# STM_BLUEPILL.net
KiCad netlist of a schematic drawn in Altium Designer
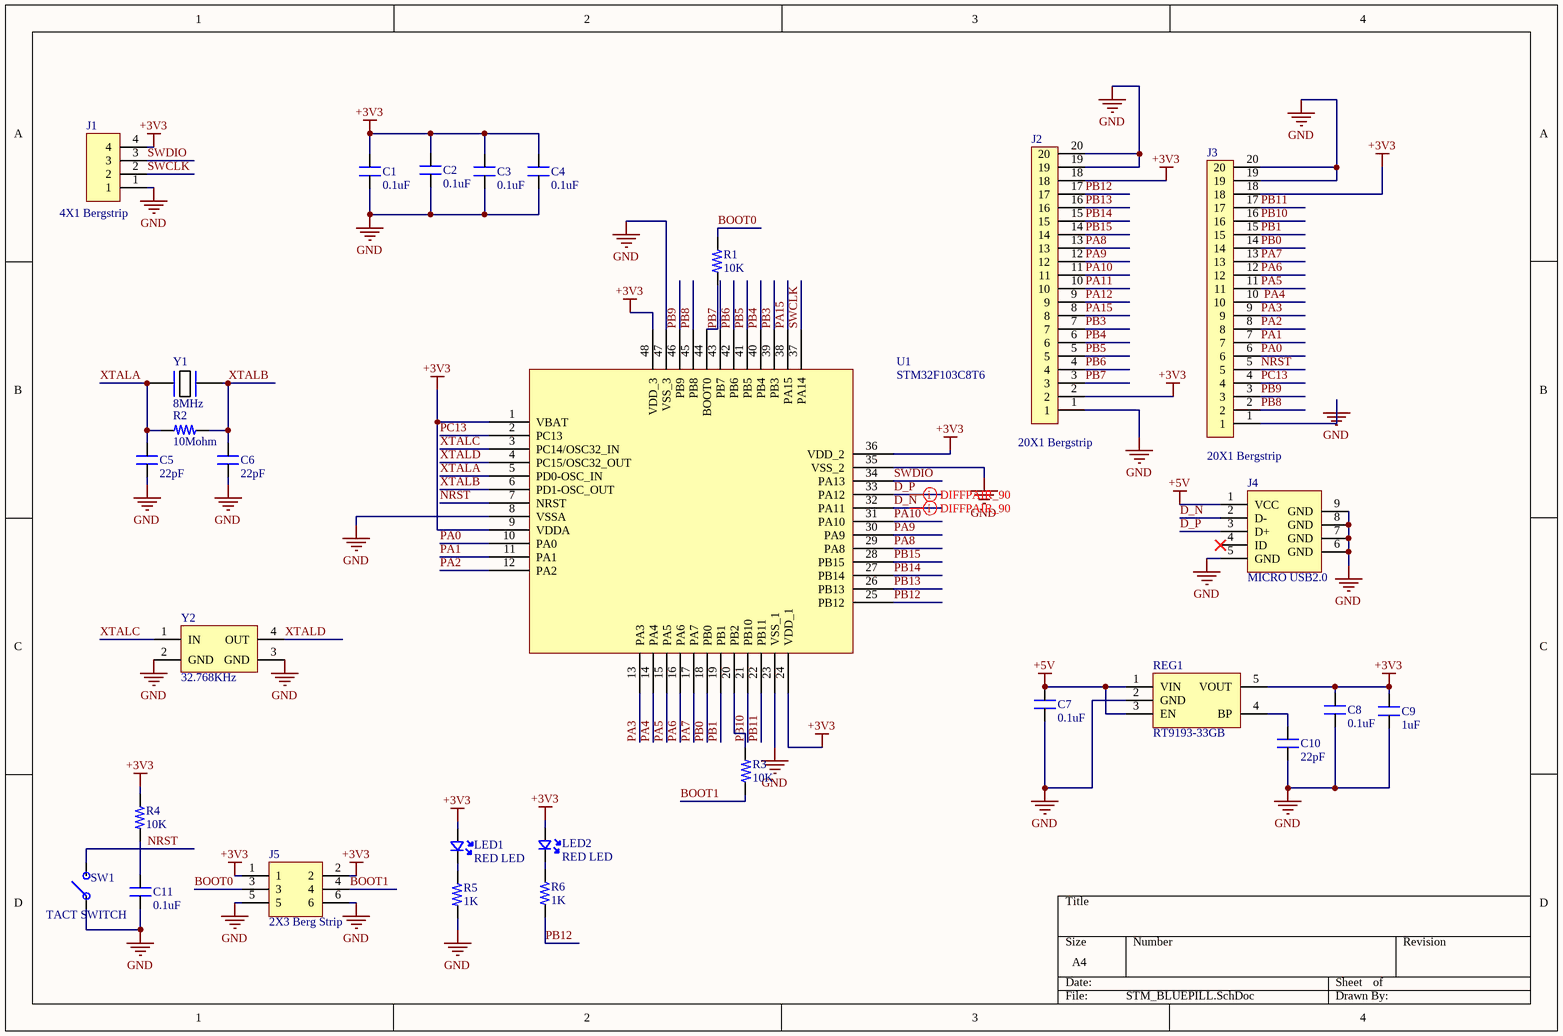
[diagram p0: STM_BLUEPILL.SchDoc]

(export (version "E")
  (design (tool "Eeschema 10.0.6"))
  (components
    (comp (ref "C1")
      (value "0.1uF")
      (footprint "CAP_0805")
      (description "0.1µF ±5% 50V Ceramic Capacitor X7R 0805 (2012 Metric)")
      (fields
        (field (name "MANUFACTURER") "KEMET")
        (field (name "MANUFACTURING PART NUMBER") "C0805C104J5RACTU")
      )
      (libsource (lib "STM_SCH_LIB") (part "CAP_0.1uF-50V-5%-0805"))
    )
    (comp (ref "C2")
      (value "0.1uF")
      (footprint "CAP_0805")
      (description "0.1µF ±5% 50V Ceramic Capacitor X7R 0805 (2012 Metric)")
      (fields
        (field (name "MANUFACTURER") "KEMET")
        (field (name "MANUFACTURING PART NUMBER") "C0805C104J5RACTU")
      )
      (libsource (lib "STM_SCH_LIB") (part "CAP_0.1uF-50V-5%-0805"))
    )
    (comp (ref "C3")
      (value "0.1uF")
      (footprint "CAP_0805")
      (description "0.1µF ±5% 50V Ceramic Capacitor X7R 0805 (2012 Metric)")
      (fields
        (field (name "MANUFACTURER") "KEMET")
        (field (name "MANUFACTURING PART NUMBER") "C0805C104J5RACTU")
      )
      (libsource (lib "STM_SCH_LIB") (part "CAP_0.1uF-50V-5%-0805"))
    )
    (comp (ref "C4")
      (value "0.1uF")
      (footprint "CAP_0805")
      (description "0.1µF ±5% 50V Ceramic Capacitor X7R 0805 (2012 Metric)")
      (fields
        (field (name "MANUFACTURER") "KEMET")
        (field (name "MANUFACTURING PART NUMBER") "C0805C104J5RACTU")
      )
      (libsource (lib "STM_SCH_LIB") (part "CAP_0.1uF-50V-5%-0805"))
    )
    (comp (ref "C5")
      (value "22pF")
      (footprint "CAP_0805")
      (description "22pF ±5% 50V Ceramic Capacitor C0G, NP0 0805 (2012 Metric)")
      (fields
        (field (name "MANUFACTURER") "KEMET")
        (field (name "MANUFACTURER PART NUMBER") "C0805C220J5GACTU")
      )
      (libsource (lib "STM_SCH_LIB") (part "CAP_22pF-50V-5%-0805"))
    )
    (comp (ref "C6")
      (value "22pF")
      (footprint "CAP_0805")
      (description "22pF ±5% 50V Ceramic Capacitor C0G, NP0 0805 (2012 Metric)")
      (fields
        (field (name "MANUFACTURER") "KEMET")
        (field (name "MANUFACTURER PART NUMBER") "C0805C220J5GACTU")
      )
      (libsource (lib "STM_SCH_LIB") (part "CAP_22pF-50V-5%-0805"))
    )
    (comp (ref "C7")
      (value "0.1uF")
      (footprint "CAP_0805")
      (description "0.1µF ±5% 50V Ceramic Capacitor X7R 0805 (2012 Metric)")
      (fields
        (field (name "MANUFACTURER") "KEMET")
        (field (name "MANUFACTURING PART NUMBER") "C0805C104J5RACTU")
      )
      (libsource (lib "STM_SCH_LIB") (part "CAP_0.1uF-50V-5%-0805"))
    )
    (comp (ref "C8")
      (value "0.1uF")
      (footprint "CAP_0805")
      (description "0.1µF ±5% 50V Ceramic Capacitor X7R 0805 (2012 Metric)")
      (fields
        (field (name "MANUFACTURER") "KEMET")
        (field (name "MANUFACTURING PART NUMBER") "C0805C104J5RACTU")
      )
      (libsource (lib "STM_SCH_LIB") (part "CAP_0.1uF-50V-5%-0805"))
    )
    (comp (ref "C9")
      (value "1uF")
      (footprint "CAP_0805")
      (description "1µF ±5% 50V Ceramic Capacitor X7R 0805 (2012 Metric)")
      (fields
        (field (name "MANUFACTURER") "Yageo")
        (field (name "MANUFACTURING PART NUMBER") "CC0805JKX7R9BB105")
      )
      (libsource (lib "STM_SCH_LIB") (part "CAP_1uF-50V-5%-0805"))
    )
    (comp (ref "C10")
      (value "22pF")
      (footprint "CAP_0805")
      (description "22pF ±5% 50V Ceramic Capacitor C0G, NP0 0805 (2012 Metric)")
      (fields
        (field (name "MANUFACTURER") "KEMET")
        (field (name "MANUFACTURER PART NUMBER") "C0805C220J5GACTU")
      )
      (libsource (lib "STM_SCH_LIB") (part "CAP_22pF-50V-5%-0805"))
    )
    (comp (ref "C11")
      (value "0.1uF")
      (footprint "CAP_0805")
      (description "0.1µF ±5% 50V Ceramic Capacitor X7R 0805 (2012 Metric)")
      (fields
        (field (name "MANUFACTURER") "KEMET")
        (field (name "MANUFACTURING PART NUMBER") "C0805C104J5RACTU")
      )
      (libsource (lib "STM_SCH_LIB") (part "CAP_0.1uF-50V-5%-0805"))
    )
    (comp (ref "J1")
      (value "4X1 Bergstrip")
      (footprint "CON4_100_40D72_TH_ST_MALE")
      (description "4 pin, 1 row, 2.54mm pitch bergstrip")
      (fields (field (name "MANUFACTURER") "NA"))
      (libsource (lib "STM_SCH_LIB") (part "CON-BS-PLG_4X1-100-TH-ST"))
    )
    (comp (ref "J2")
      (value "20X1 Bergstrip")
      (footprint "CON20_100_40D72_TH_ST")
      (description "20 pin, 1 row, 2.54mm pitch bergstrip")
      (fields (field (name "MANUFACTURER") "NA"))
      (libsource (lib "STM_SCH_LIB") (part "CON-BS-PLG_20X1-100-TH-ST"))
    )
    (comp (ref "J3")
      (value "20X1 Bergstrip")
      (footprint "CON20_100_40D72_TH_ST")
      (description "20 pin, 1 row, 2.54mm pitch bergstrip")
      (fields (field (name "MANUFACTURER") "NA"))
      (libsource (lib "STM_SCH_LIB") (part "CON-BS-PLG_20X1-100-TH-ST"))
    )
    (comp (ref "J4")
      (value "MICRO USB2.0")
      (footprint "CON_10118192-0001LF_SMD")
      (description "USB - micro B USB 2.0 Receptacle Connector 5 Position Surface Mount, Right Angle")
      (fields
        (field (name "MANUFACTURER") "Amphenol ICC (FCI)")
        (field (name "MANUFACTURING PART NUMBER") "10118192-0002LF")
      )
      (libsource (lib "STM_SCH_LIB") (part "CON-USB_10118192-0002LF-SMD"))
    )
    (comp (ref "J5")
      (value "2X3 Berg Strip")
      (footprint "CON6_100_59D78_TH_ST_Duplicate")
      (description "6 pin, 2 row, 2.54mm pitch bergstrip")
      (fields (field (name "MANUFACTURER") "NA"))
      (libsource (lib "STM_SCH_LIB") (part "CON-BS-PLG_2X3-100-TH-ST"))
    )
    (comp (ref "LED1")
      (value "RED LED")
      (footprint "LED_0805")
      (description "Red 621nm LED Indication - Discrete 2V 0805 (2012 Metric)")
      (fields
        (field (name "MANUFACTURER") "Lite-On Inc.")
        (field (name "MANUFACTURER PART NUMBER") "LTST-C170EKT")
      )
      (libsource (lib "STM_SCH_LIB") (part "LED-RED_10mA-0805"))
    )
    (comp (ref "LED2")
      (value "RED LED")
      (footprint "LED_0805")
      (description "Red 621nm LED Indication - Discrete 2V 0805 (2012 Metric)")
      (fields
        (field (name "MANUFACTURER") "Lite-On Inc.")
        (field (name "MANUFACTURER PART NUMBER") "LTST-C170EKT")
      )
      (libsource (lib "STM_SCH_LIB") (part "LED-RED_10mA-0805"))
    )
    (comp (ref "R1")
      (value "10K")
      (footprint "RES_0805")
      (description "10 kOhms ±1% 0.125W, 1/8W Chip Resistor 0805 (2012 Metric) Moisture Resistant Thick Film")
      (fields
        (field (name "MANUFACTURER") "Yageo")
        (field (name "MANUFACTURING PART NUMBER") "RC0805FR-0710KL")
      )
      (libsource (lib "STM_SCH_LIB") (part "RES_10K-0.125W-1%-0805"))
    )
    (comp (ref "R2")
      (value "10Mohm")
      (footprint "RES_0805")
      (fields
        (field (name "MANUFACTURER") "Rohm Semiconductor")
        (field (name "MANUFACTURING PART NUMBER") "KTR10EZPF1005")
      )
      (libsource (lib "STM_SCH_LIB") (part "RES_10MOHM-0.125W-1%-0805"))
    )
    (comp (ref "R3")
      (value "10K")
      (footprint "RES_0805")
      (description "10 kOhms ±1% 0.125W, 1/8W Chip Resistor 0805 (2012 Metric) Moisture Resistant Thick Film")
      (fields
        (field (name "MANUFACTURER") "Yageo")
        (field (name "MANUFACTURING PART NUMBER") "RC0805FR-0710KL")
      )
      (libsource (lib "STM_SCH_LIB") (part "RES_10K-0.125W-1%-0805"))
    )
    (comp (ref "R4")
      (value "10K")
      (footprint "RES_0805")
      (description "10 kOhms ±1% 0.125W, 1/8W Chip Resistor 0805 (2012 Metric) Moisture Resistant Thick Film")
      (fields
        (field (name "MANUFACTURER") "Yageo")
        (field (name "MANUFACTURING PART NUMBER") "RC0805FR-0710KL")
      )
      (libsource (lib "STM_SCH_LIB") (part "RES_10K-0.125W-1%-0805"))
    )
    (comp (ref "R5")
      (value "1K")
      (footprint "RES_0805")
      (description "1 kOhms ±1% 0.125W, 1/8W Chip Resistor 0805 (2012 Metric) Moisture Resistant Thick Film")
      (fields (field (name "MANUFACTURER") "垈㎵á") (field (name "MANUFACTURER PART NUMBER") "RC0805FR-071KL"))
      (libsource (lib "STM_SCH_LIB") (part "RES_1K-0.125W-1%-0805"))
    )
    (comp (ref "R6")
      (value "1K")
      (footprint "RES_0805")
      (description "1 kOhms ±1% 0.125W, 1/8W Chip Resistor 0805 (2012 Metric) Moisture Resistant Thick Film")
      (fields (field (name "MANUFACTURER") "垈㎵á") (field (name "MANUFACTURER PART NUMBER") "RC0805FR-071KL"))
      (libsource (lib "STM_SCH_LIB") (part "RES_1K-0.125W-1%-0805"))
    )
    (comp (ref "REG1")
      (value "RT9193-33GB")
      (footprint "SOT23-5")
      (description "Linear Voltage Regulator IC 1 Output 300mA SOT-23-5")
      (fields (field (name "MANUFACTURER") "Richtek USA Inc."))
      (libsource (lib "STM_SCH_LIB") (part "REG_3.3V-5.5V-0.3A-SOT-23-5"))
    )
    (comp (ref "SW1")
      (value "TACT SWITCH")
      (footprint "SW_342_SMD")
      (description "Tactile Switch SPST-NO Top Actuated Surface Mount")
      (fields (field (name "MANUFACTURER") "C&K") (field (name "MANUFACTURING PART NUMBER") "KSR223GLFG"))
      (libsource (lib "STM_SCH_LIB") (part "SW_KSR223GLFG-SMD"))
    )
    (comp (ref "U1")
      (value "STM32F103C8T6")
      (footprint "LQFP-48_19.6_393_58X11_SMD")
      (description "ARM® Cortex®-M3 STM32F1 Microcontroller IC 32-Bit 72MHz 64KB (64K x 8) FLASH")
      (fields (field (name "MANUFACTURER") "STMicroelectronics"))
      (libsource (lib "STM_SCH_LIB") (part "IC-STM32F103C8T6 _1"))
    )
    (comp (ref "Y1")
      (value "8MHz")
      (footprint "XTAL_314_240X47_SMD")
      (description "Crystals 8MHz 22pF -20C 70C")
      (fields
        (field (name "MANUFACTURER") "IQD Frequency Products")
        (field (name "MANUFACTURING PART NUMBER") "LFXTAL030234Reel")
      )
      (libsource (lib "STM_SCH_LIB") (part "XTAL_8MHZ-LFXTAL030234"))
    )
    (comp (ref "Y2")
      (value "32.768KHz")
      (footprint "XTAL_MC-405 32.7680K-G3")
      (description "Crystals SMD AT XTL MHZ +/-50PPM 12.5 PF 250 T/R")
      (fields
        (field (name "MANUFACTURER") "Epson")
        (field (name "MANUFACTURING PART NUMBER") "MC-405 32.7680K-G3: ROHS")
      )
      (libsource (lib "STM_SCH_LIB") (part "XTAL_32.768KHz-MC-405 32.7680K-G3"))
    )
  )
  (nets
    (net (code "1") (name "+3V3") (class "Default")
      (node (ref "C1") (pin "2") (pinfunction "2_2") (pintype "passive"))
      (node (ref "C2") (pin "2") (pinfunction "2_2") (pintype "passive"))
      (node (ref "C3") (pin "2") (pinfunction "2_2") (pintype "passive"))
      (node (ref "C4") (pin "2") (pinfunction "2_2") (pintype "passive"))
      (node (ref "C8") (pin "2") (pinfunction "2_2") (pintype "passive"))
      (node (ref "C9") (pin "2") (pinfunction "2_2") (pintype "passive"))
      (node (ref "J1") (pin "4") (pinfunction "4_4") (pintype "passive"))
      (node (ref "J2") (pin "18") (pinfunction "18_18") (pintype "passive"))
      (node (ref "J2") (pin "2") (pinfunction "2_2") (pintype "passive"))
      (node (ref "J3") (pin "18") (pinfunction "18_18") (pintype "passive"))
      (node (ref "J5") (pin "1") (pinfunction "1_1") (pintype "passive"))
      (node (ref "J5") (pin "2") (pinfunction "2_2") (pintype "passive"))
      (node (ref "LED1") (pin "A") (pinfunction "A_A") (pintype "passive"))
      (node (ref "LED2") (pin "A") (pinfunction "A_A") (pintype "passive"))
      (node (ref "R4") (pin "2") (pinfunction "2_2") (pintype "passive"))
      (node (ref "REG1") (pin "5") (pinfunction "VOUT_5") (pintype "passive"))
      (node (ref "U1") (pin "1") (pinfunction "VBAT_1") (pintype "passive"))
      (node (ref "U1") (pin "24") (pinfunction "VDD_1_24") (pintype "passive"))
      (node (ref "U1") (pin "36") (pinfunction "VDD_2_36") (pintype "passive"))
      (node (ref "U1") (pin "48") (pinfunction "VDD_3_48") (pintype "passive"))
      (node (ref "U1") (pin "9") (pinfunction "VDDA_9") (pintype "passive"))
    )
    (net (code "2") (name "+5V") (class "Default")
      (node (ref "C7") (pin "2") (pinfunction "2_2") (pintype "passive"))
      (node (ref "J4") (pin "1") (pinfunction "VCC_1") (pintype "passive"))
      (node (ref "REG1") (pin "1") (pinfunction "VIN_1") (pintype "passive"))
      (node (ref "REG1") (pin "3") (pinfunction "EN_3") (pintype "passive"))
    )
    (net (code "3") (name "/BOOT0") (class "Default")
      (node (ref "J5") (pin "3") (pinfunction "3_3") (pintype "passive"))
      (node (ref "R1") (pin "2") (pinfunction "2_2") (pintype "passive"))
    )
    (net (code "4") (name "/BOOT1") (class "Default")
      (node (ref "J5") (pin "4") (pinfunction "4_4") (pintype "passive"))
      (node (ref "R3") (pin "2") (pinfunction "2_2") (pintype "passive"))
    )
    (net (code "5") (name "/D_N") (class "Default")
      (node (ref "U1") (pin "32") (pinfunction "PA11_32") (pintype "passive"))
    )
    (net (code "6") (name "/D_P") (class "Default")
      (node (ref "J4") (pin "3") (pinfunction "D+_3") (pintype "passive"))
      (node (ref "U1") (pin "33") (pinfunction "PA12_33") (pintype "passive"))
    )
    (net (code "7") (name "/D_~{N}") (class "Default")
      (node (ref "J4") (pin "2") (pinfunction "D-_2") (pintype "passive"))
    )
    (net (code "8") (name "/NRST") (class "Default")
      (node (ref "J3") (pin "5") (pinfunction "5_5") (pintype "passive"))
      (node (ref "SW1") (pin "2") (pinfunction "2_2") (pintype "passive"))
      (node (ref "U1") (pin "7") (pinfunction "NRST_7") (pintype "passive"))
    )
    (net (code "9") (name "/PA0") (class "Default")
      (node (ref "J3") (pin "6") (pinfunction "6_6") (pintype "passive"))
      (node (ref "U1") (pin "10") (pinfunction "PA0_10") (pintype "passive"))
    )
    (net (code "10") (name "/PA1") (class "Default")
      (node (ref "J3") (pin "7") (pinfunction "7_7") (pintype "passive"))
      (node (ref "U1") (pin "11") (pinfunction "PA1_11") (pintype "passive"))
    )
    (net (code "11") (name "/PA2") (class "Default")
      (node (ref "J3") (pin "8") (pinfunction "8_8") (pintype "passive"))
      (node (ref "U1") (pin "12") (pinfunction "PA2_12") (pintype "passive"))
    )
    (net (code "12") (name "/PA3") (class "Default")
      (node (ref "J3") (pin "9") (pinfunction "9_9") (pintype "passive"))
      (node (ref "U1") (pin "13") (pinfunction "PA3_13") (pintype "passive"))
    )
    (net (code "13") (name "/PA4") (class "Default")
      (node (ref "J3") (pin "10") (pinfunction "10_10") (pintype "passive"))
      (node (ref "U1") (pin "14") (pinfunction "PA4_14") (pintype "passive"))
    )
    (net (code "14") (name "/PA5") (class "Default")
      (node (ref "J3") (pin "11") (pinfunction "11_11") (pintype "passive"))
      (node (ref "U1") (pin "15") (pinfunction "PA5_15") (pintype "passive"))
    )
    (net (code "15") (name "/PA6") (class "Default")
      (node (ref "J3") (pin "12") (pinfunction "12_12") (pintype "passive"))
      (node (ref "U1") (pin "16") (pinfunction "PA6_16") (pintype "passive"))
    )
    (net (code "16") (name "/PA7") (class "Default")
      (node (ref "J3") (pin "13") (pinfunction "13_13") (pintype "passive"))
      (node (ref "U1") (pin "17") (pinfunction "PA7_17") (pintype "passive"))
    )
    (net (code "17") (name "/PA8") (class "Default")
      (node (ref "J2") (pin "13") (pinfunction "13_13") (pintype "passive"))
      (node (ref "U1") (pin "29") (pinfunction "PA8_29") (pintype "passive"))
    )
    (net (code "18") (name "/PA9") (class "Default")
      (node (ref "J2") (pin "12") (pinfunction "12_12") (pintype "passive"))
      (node (ref "U1") (pin "30") (pinfunction "PA9_30") (pintype "passive"))
    )
    (net (code "19") (name "/PA10") (class "Default")
      (node (ref "J2") (pin "11") (pinfunction "11_11") (pintype "passive"))
      (node (ref "U1") (pin "31") (pinfunction "PA10_31") (pintype "passive"))
    )
    (net (code "20") (name "/PA11") (class "Default")
      (node (ref "J2") (pin "10") (pinfunction "10_10") (pintype "passive"))
    )
    (net (code "21") (name "/PA12") (class "Default")
      (node (ref "J2") (pin "9") (pinfunction "9_9") (pintype "passive"))
    )
    (net (code "22") (name "/PA15") (class "Default")
      (node (ref "J2") (pin "8") (pinfunction "8_8") (pintype "passive"))
      (node (ref "U1") (pin "38") (pinfunction "PA15_38") (pintype "passive"))
    )
    (net (code "23") (name "/PB0") (class "Default")
      (node (ref "J3") (pin "14") (pinfunction "14_14") (pintype "passive"))
      (node (ref "U1") (pin "18") (pinfunction "PB0_18") (pintype "passive"))
    )
    (net (code "24") (name "/PB1") (class "Default")
      (node (ref "J3") (pin "15") (pinfunction "15_15") (pintype "passive"))
      (node (ref "U1") (pin "19") (pinfunction "PB1_19") (pintype "passive"))
    )
    (net (code "25") (name "/PB3") (class "Default")
      (node (ref "J2") (pin "7") (pinfunction "7_7") (pintype "passive"))
      (node (ref "U1") (pin "39") (pinfunction "PB3_39") (pintype "passive"))
    )
    (net (code "26") (name "/PB4") (class "Default")
      (node (ref "J2") (pin "6") (pinfunction "6_6") (pintype "passive"))
      (node (ref "U1") (pin "40") (pinfunction "PB4_40") (pintype "passive"))
    )
    (net (code "27") (name "/PB5") (class "Default")
      (node (ref "J2") (pin "5") (pinfunction "5_5") (pintype "passive"))
      (node (ref "U1") (pin "41") (pinfunction "PB5_41") (pintype "passive"))
    )
    (net (code "28") (name "/PB6") (class "Default")
      (node (ref "J2") (pin "4") (pinfunction "4_4") (pintype "passive"))
      (node (ref "U1") (pin "42") (pinfunction "PB6_42") (pintype "passive"))
    )
    (net (code "29") (name "/PB7") (class "Default")
      (node (ref "J2") (pin "3") (pinfunction "3_3") (pintype "passive"))
      (node (ref "U1") (pin "43") (pinfunction "PB7_43") (pintype "passive"))
    )
    (net (code "30") (name "/PB8") (class "Default")
      (node (ref "J3") (pin "2") (pinfunction "2_2") (pintype "passive"))
      (node (ref "U1") (pin "45") (pinfunction "PB8_45") (pintype "passive"))
    )
    (net (code "31") (name "/PB9") (class "Default")
      (node (ref "J3") (pin "3") (pinfunction "3_3") (pintype "passive"))
      (node (ref "U1") (pin "46") (pinfunction "PB9_46") (pintype "passive"))
    )
    (net (code "32") (name "/PB10") (class "Default")
      (node (ref "J3") (pin "16") (pinfunction "16_16") (pintype "passive"))
      (node (ref "U1") (pin "21") (pinfunction "PB10_21") (pintype "passive"))
    )
    (net (code "33") (name "/PB11") (class "Default")
      (node (ref "J3") (pin "17") (pinfunction "17_17") (pintype "passive"))
      (node (ref "U1") (pin "22") (pinfunction "PB11_22") (pintype "passive"))
    )
    (net (code "34") (name "/PB12") (class "Default")
      (node (ref "J2") (pin "17") (pinfunction "17_17") (pintype "passive"))
      (node (ref "R6") (pin "1") (pinfunction "1_1") (pintype "passive"))
      (node (ref "U1") (pin "25") (pinfunction "PB12_25") (pintype "passive"))
    )
    (net (code "35") (name "/PB13") (class "Default")
      (node (ref "J2") (pin "16") (pinfunction "16_16") (pintype "passive"))
      (node (ref "U1") (pin "26") (pinfunction "PB13_26") (pintype "passive"))
    )
    (net (code "36") (name "/PB14") (class "Default")
      (node (ref "J2") (pin "15") (pinfunction "15_15") (pintype "passive"))
      (node (ref "U1") (pin "27") (pinfunction "PB14_27") (pintype "passive"))
    )
    (net (code "37") (name "/PB15") (class "Default")
      (node (ref "J2") (pin "14") (pinfunction "14_14") (pintype "passive"))
      (node (ref "U1") (pin "28") (pinfunction "PB15_28") (pintype "passive"))
    )
    (net (code "38") (name "/PC13") (class "Default")
      (node (ref "J3") (pin "4") (pinfunction "4_4") (pintype "passive"))
      (node (ref "U1") (pin "2") (pinfunction "PC13_2") (pintype "passive"))
    )
    (net (code "39") (name "/SWCLK") (class "Default")
      (node (ref "J1") (pin "2") (pinfunction "2_2") (pintype "passive"))
      (node (ref "U1") (pin "37") (pinfunction "PA14_37") (pintype "passive"))
    )
    (net (code "40") (name "/SWDIO") (class "Default")
      (node (ref "J1") (pin "3") (pinfunction "3_3") (pintype "passive"))
      (node (ref "U1") (pin "34") (pinfunction "PA13_34") (pintype "passive"))
    )
    (net (code "41") (name "/XTALA") (class "Default")
      (node (ref "C5") (pin "2") (pinfunction "2_2") (pintype "passive"))
      (node (ref "R2") (pin "1") (pinfunction "1_1") (pintype "passive"))
      (node (ref "U1") (pin "5") (pinfunction "PD0-OSC_IN_5") (pintype "passive"))
      (node (ref "Y1") (pin "1") (pinfunction "1_1") (pintype "passive"))
    )
    (net (code "42") (name "/XTALB") (class "Default")
      (node (ref "C6") (pin "2") (pinfunction "2_2") (pintype "passive"))
      (node (ref "R2") (pin "2") (pinfunction "2_2") (pintype "passive"))
      (node (ref "U1") (pin "6") (pinfunction "PD1-OSC_OUT_6") (pintype "passive"))
      (node (ref "Y1") (pin "2") (pinfunction "2_2") (pintype "passive"))
    )
    (net (code "43") (name "/XTALC") (class "Default")
      (node (ref "U1") (pin "3") (pinfunction "PC14/OSC32_IN_3") (pintype "passive"))
      (node (ref "Y2") (pin "1") (pinfunction "IN_1") (pintype "passive"))
    )
    (net (code "44") (name "/XTALD") (class "Default")
      (node (ref "U1") (pin "4") (pinfunction "PC15/OSC32_OUT_4") (pintype "passive"))
      (node (ref "Y2") (pin "4") (pinfunction "OUT_4") (pintype "passive"))
    )
    (net (code "45") (name "GND") (class "Default")
      (node (ref "C1") (pin "1") (pinfunction "1_1") (pintype "passive"))
      (node (ref "C10") (pin "1") (pinfunction "1_1") (pintype "passive"))
      (node (ref "C11") (pin "1") (pinfunction "1_1") (pintype "passive"))
      (node (ref "C2") (pin "1") (pinfunction "1_1") (pintype "passive"))
      (node (ref "C3") (pin "1") (pinfunction "1_1") (pintype "passive"))
      (node (ref "C4") (pin "1") (pinfunction "1_1") (pintype "passive"))
      (node (ref "C5") (pin "1") (pinfunction "1_1") (pintype "passive"))
      (node (ref "C6") (pin "1") (pinfunction "1_1") (pintype "passive"))
      (node (ref "C7") (pin "1") (pinfunction "1_1") (pintype "passive"))
      (node (ref "C8") (pin "1") (pinfunction "1_1") (pintype "passive"))
      (node (ref "C9") (pin "1") (pinfunction "1_1") (pintype "passive"))
      (node (ref "J1") (pin "1") (pinfunction "1_1") (pintype "passive"))
      (node (ref "J2") (pin "1") (pinfunction "1_1") (pintype "passive"))
      (node (ref "J2") (pin "19") (pinfunction "19_19") (pintype "passive"))
      (node (ref "J2") (pin "20") (pinfunction "20_20") (pintype "passive"))
      (node (ref "J3") (pin "1") (pinfunction "1_1") (pintype "passive"))
      (node (ref "J3") (pin "19") (pinfunction "19_19") (pintype "passive"))
      (node (ref "J3") (pin "20") (pinfunction "20_20") (pintype "passive"))
      (node (ref "J4") (pin "5") (pinfunction "GND_5") (pintype "passive"))
      (node (ref "J4") (pin "6") (pinfunction "GND_6") (pintype "passive"))
      (node (ref "J4") (pin "7") (pinfunction "GND_7") (pintype "passive"))
      (node (ref "J4") (pin "8") (pinfunction "GND_8") (pintype "passive"))
      (node (ref "J4") (pin "9") (pinfunction "GND_9") (pintype "passive"))
      (node (ref "J5") (pin "5") (pinfunction "5_5") (pintype "passive"))
      (node (ref "J5") (pin "6") (pinfunction "6_6") (pintype "passive"))
      (node (ref "R5") (pin "1") (pinfunction "1_1") (pintype "passive"))
      (node (ref "REG1") (pin "2") (pinfunction "GND_2") (pintype "passive"))
      (node (ref "SW1") (pin "1") (pinfunction "1_1") (pintype "passive"))
      (node (ref "U1") (pin "23") (pinfunction "VSS_1_23") (pintype "passive"))
      (node (ref "U1") (pin "35") (pinfunction "VSS_2_35") (pintype "passive"))
      (node (ref "U1") (pin "47") (pinfunction "VSS_3_47") (pintype "passive"))
      (node (ref "U1") (pin "8") (pinfunction "VSSA_8") (pintype "passive"))
      (node (ref "Y2") (pin "2") (pinfunction "GND_2") (pintype "passive"))
      (node (ref "Y2") (pin "3") (pinfunction "GND_3") (pintype "passive"))
    )
    (net (code "46") (name "Net-(C11-Pad2)") (class "Default")
      (node (ref "C11") (pin "2") (pinfunction "2_2") (pintype "passive"))
      (node (ref "R4") (pin "1") (pinfunction "1_1") (pintype "passive"))
    )
    (net (code "47") (name "Net-(LED1-PadK)") (class "Default")
      (node (ref "LED1") (pin "K") (pinfunction "K_K") (pintype "passive"))
      (node (ref "R5") (pin "2") (pinfunction "2_2") (pintype "passive"))
    )
    (net (code "48") (name "Net-(LED2-PadK)") (class "Default")
      (node (ref "LED2") (pin "K") (pinfunction "K_K") (pintype "passive"))
      (node (ref "R6") (pin "2") (pinfunction "2_2") (pintype "passive"))
    )
    (net (code "49") (name "Net-(REG1-BP)") (class "Default")
      (node (ref "C10") (pin "2") (pinfunction "2_2") (pintype "passive"))
      (node (ref "REG1") (pin "4") (pinfunction "BP_4") (pintype "passive"))
    )
    (net (code "50") (name "Net-(U1-BOOT0)") (class "Default")
      (node (ref "R1") (pin "1") (pinfunction "1_1") (pintype "passive"))
      (node (ref "U1") (pin "44") (pinfunction "BOOT0_44") (pintype "passive"))
    )
    (net (code "51") (name "Net-(U1-PB2)") (class "Default")
      (node (ref "R3") (pin "1") (pinfunction "1_1") (pintype "passive"))
      (node (ref "U1") (pin "20") (pinfunction "PB2_20") (pintype "passive"))
    )
    (net (code "52") (name "unconnected-(J4-ID-Pad4)") (class "Default")
      (node (ref "J4") (pin "4") (pinfunction "ID_4") (pintype "passive+no_connect"))
    )
  )
)
